# schematic.net
KiCad netlist of a schematic drawn in Altium Designer
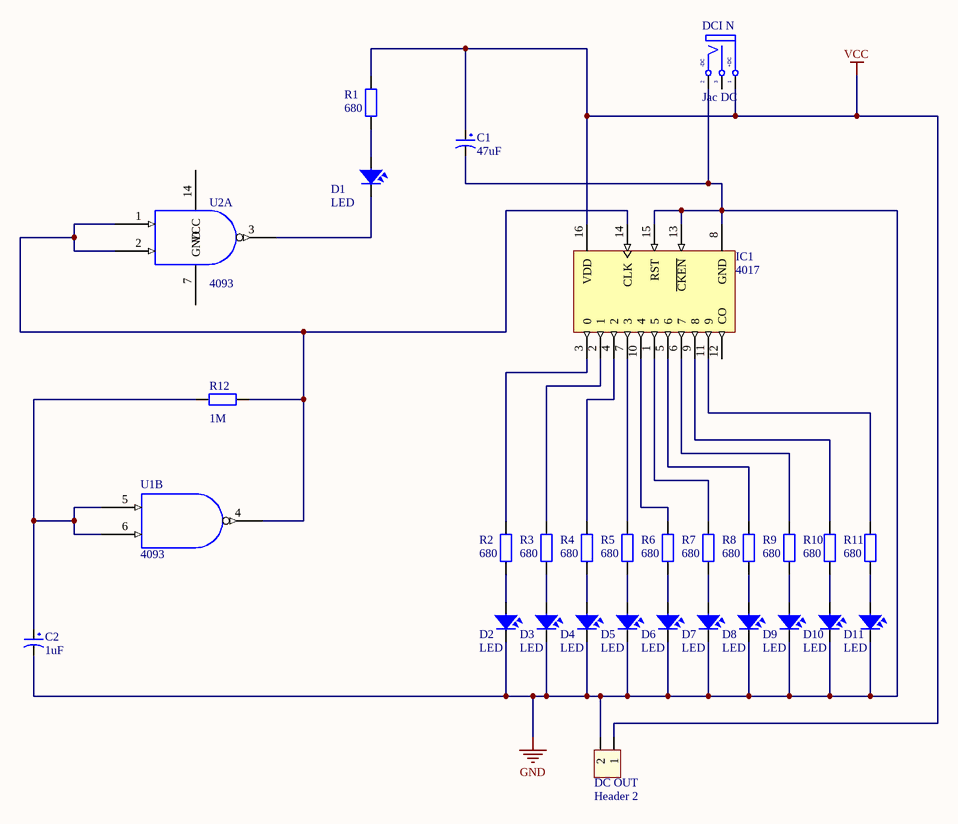
[diagram p0: schematic.SchDoc]

(export (version "E")
  (design (tool "Eeschema 10.0.6"))
  (components
    (comp (ref "C1")
      (value "47uF")
      (footprint "CP1/2.5")
      (description "C 47uF/50V , 220uF/16V")
      (libsource (lib "My Library") (part "CP2"))
    )
    (comp (ref "C2")
      (value "1uF")
      (footprint "CP1/2.5")
      (description "C 47uF/50V , 220uF/16V")
      (libsource (lib "My Library") (part "CP2"))
    )
    (comp (ref "D1")
      (value "LED")
      (footprint "LED-3")
      (description "LED Single colour Green and Red")
      (libsource (lib "My Library") (part "LED"))
    )
    (comp (ref "D2")
      (value "LED")
      (footprint "LED-3")
      (description "LED Single colour Green and Red")
      (libsource (lib "My Library") (part "LED"))
    )
    (comp (ref "D3")
      (value "LED")
      (footprint "LED-3")
      (description "LED Single colour Green and Red")
      (libsource (lib "My Library") (part "LED"))
    )
    (comp (ref "D4")
      (value "LED")
      (footprint "LED-3")
      (description "LED Single colour Green and Red")
      (libsource (lib "My Library") (part "LED"))
    )
    (comp (ref "D5")
      (value "LED")
      (footprint "LED-3")
      (description "LED Single colour Green and Red")
      (libsource (lib "My Library") (part "LED"))
    )
    (comp (ref "D6")
      (value "LED")
      (footprint "LED-3")
      (description "LED Single colour Green and Red")
      (libsource (lib "My Library") (part "LED"))
    )
    (comp (ref "D7")
      (value "LED")
      (footprint "LED-3")
      (description "LED Single colour Green and Red")
      (libsource (lib "My Library") (part "LED"))
    )
    (comp (ref "D8")
      (value "LED")
      (footprint "LED-3")
      (description "LED Single colour Green and Red")
      (libsource (lib "My Library") (part "LED"))
    )
    (comp (ref "D9")
      (value "LED")
      (footprint "LED-3")
      (description "LED Single colour Green and Red")
      (libsource (lib "My Library") (part "LED"))
    )
    (comp (ref "D10")
      (value "LED")
      (footprint "LED-3")
      (description "LED Single colour Green and Red")
      (libsource (lib "My Library") (part "LED"))
    )
    (comp (ref "D11")
      (value "LED")
      (footprint "LED-3")
      (description "LED Single colour Green and Red")
      (libsource (lib "My Library") (part "LED"))
    )
    (comp (ref "DC OUT")
      (value "Header 2")
      (footprint "HED2")
      (description "Header 2 (Green)")
      (libsource (lib "My Library") (part "Hed2"))
    )
    (comp (ref "DCI N")
      (value "Jac DC")
      (footprint "DC-IN")
      (description "Jac DC input")
      (libsource (lib "My Library") (part "DCIN"))
    )
    (comp (ref "IC1")
      (value "4017")
      (footprint "DIP16/W0.3")
      (description "Decade Counter/Divider with 10 Decoded Outputs")
      (fields (field (name "DESIGNED BY") "VanDungEvn"))
      (libsource (lib "My Library") (part "4017"))
    )
    (comp (ref "R1")
      (value "680")
      (footprint "DIEN TRO 1/4 W")
      (description "Resistor")
      (fields (field (name "PUBLISHER") "Altium Limited"))
      (libsource (lib "My Library") (part "Res 1/4 W"))
    )
    (comp (ref "R2")
      (value "680")
      (footprint "DIEN TRO 1/4 W")
      (description "Resistor")
      (fields (field (name "PUBLISHER") "Altium Limited"))
      (libsource (lib "My Library") (part "Res 1/4 W"))
    )
    (comp (ref "R3")
      (value "680")
      (footprint "DIEN TRO 1/4 W")
      (description "Resistor")
      (fields (field (name "PUBLISHER") "Altium Limited"))
      (libsource (lib "My Library") (part "Res 1/4 W"))
    )
    (comp (ref "R4")
      (value "680")
      (footprint "DIEN TRO 1/4 W")
      (description "Resistor")
      (fields (field (name "PUBLISHER") "Altium Limited"))
      (libsource (lib "My Library") (part "Res 1/4 W"))
    )
    (comp (ref "R5")
      (value "680")
      (footprint "DIEN TRO 1/4 W")
      (description "Resistor")
      (fields (field (name "PUBLISHER") "Altium Limited"))
      (libsource (lib "My Library") (part "Res 1/4 W"))
    )
    (comp (ref "R6")
      (value "680")
      (footprint "DIEN TRO 1/4 W")
      (description "Resistor")
      (fields (field (name "PUBLISHER") "Altium Limited"))
      (libsource (lib "My Library") (part "Res 1/4 W"))
    )
    (comp (ref "R7")
      (value "680")
      (footprint "DIEN TRO 1/4 W")
      (description "Resistor")
      (fields (field (name "PUBLISHER") "Altium Limited"))
      (libsource (lib "My Library") (part "Res 1/4 W"))
    )
    (comp (ref "R8")
      (value "680")
      (footprint "DIEN TRO 1/4 W")
      (description "Resistor")
      (fields (field (name "PUBLISHER") "Altium Limited"))
      (libsource (lib "My Library") (part "Res 1/4 W"))
    )
    (comp (ref "R9")
      (value "680")
      (footprint "DIEN TRO 1/4 W")
      (description "Resistor")
      (fields (field (name "PUBLISHER") "Altium Limited"))
      (libsource (lib "My Library") (part "Res 1/4 W"))
    )
    (comp (ref "R10")
      (value "680")
      (footprint "DIEN TRO 1/4 W")
      (description "Resistor")
      (fields (field (name "PUBLISHER") "Altium Limited"))
      (libsource (lib "My Library") (part "Res 1/4 W"))
    )
    (comp (ref "R11")
      (value "680")
      (footprint "DIEN TRO 1/4 W")
      (description "Resistor")
      (fields (field (name "PUBLISHER") "Altium Limited"))
      (libsource (lib "My Library") (part "Res 1/4 W"))
    )
    (comp (ref "R12")
      (value "1M")
      (footprint "DIEN TRO 1/4 W")
      (description "Resistor")
      (fields (field (name "PUBLISHER") "Altium Limited"))
      (libsource (lib "") (part "Res 1/4 W_1"))
    )
    (comp (ref "U1")
      (value "4093")
      (footprint "DIP14")
      (description "Quad 2-INPUT NAND SCHMITT TRIGGER")
      (libsource (lib "My Library") (part "4093"))
    )
    (comp (ref "U2")
      (value "4093")
      (footprint "DIP14")
      (description "Quad 2-INPUT NAND SCHMITT TRIGGER")
      (libsource (lib "My Library") (part "4093"))
    )
  )
  (nets
    (net (code "1") (name "GND") (class "Default")
      (node (ref "C1") (pin "2") (pinfunction "2_2") (pintype "passive"))
      (node (ref "C2") (pin "2") (pinfunction "2_2") (pintype "passive"))
      (node (ref "D10") (pin "2") (pinfunction "2_2") (pintype "passive"))
      (node (ref "D11") (pin "2") (pinfunction "2_2") (pintype "passive"))
      (node (ref "D2") (pin "2") (pinfunction "2_2") (pintype "passive"))
      (node (ref "D3") (pin "2") (pinfunction "2_2") (pintype "passive"))
      (node (ref "D4") (pin "2") (pinfunction "2_2") (pintype "passive"))
      (node (ref "D5") (pin "2") (pinfunction "2_2") (pintype "passive"))
      (node (ref "D6") (pin "2") (pinfunction "2_2") (pintype "passive"))
      (node (ref "D7") (pin "2") (pinfunction "2_2") (pintype "passive"))
      (node (ref "D8") (pin "2") (pinfunction "2_2") (pintype "passive"))
      (node (ref "D9") (pin "2") (pinfunction "2_2") (pintype "passive"))
      (node (ref "DC OUT") (pin "2") (pinfunction "2_2") (pintype "passive"))
      (node (ref "DCI N") (pin "2") (pinfunction "TN_2") (pintype "passive"))
      (node (ref "IC1") (pin "13") (pinfunction "~{CKEN}_13") (pintype "input"))
      (node (ref "IC1") (pin "15") (pinfunction "RST_15") (pintype "input"))
      (node (ref "IC1") (pin "8") (pinfunction "GND_8") (pintype "power_in"))
    )
    (net (code "2") (name "Net-(C2-Pad1)") (class "Default")
      (node (ref "C2") (pin "1") (pinfunction "1_1") (pintype "passive"))
      (node (ref "R12") (pin "2") (pinfunction "2_2") (pintype "passive"))
      (node (ref "U1") (pin "5") (pintype "input"))
      (node (ref "U1") (pin "6") (pintype "input"))
    )
    (net (code "3") (name "Net-(D1-Pad1)") (class "Default")
      (node (ref "D1") (pin "1") (pinfunction "1_1") (pintype "passive"))
      (node (ref "R1") (pin "1") (pinfunction "1_1") (pintype "passive"))
    )
    (net (code "4") (name "Net-(D1-Pad2)") (class "Default")
      (node (ref "D1") (pin "2") (pinfunction "2_2") (pintype "passive"))
      (node (ref "U2") (pin "3") (pintype "output"))
    )
    (net (code "5") (name "Net-(D2-Pad1)") (class "Default")
      (node (ref "D2") (pin "1") (pinfunction "1_1") (pintype "passive"))
      (node (ref "R2") (pin "1") (pinfunction "1_1") (pintype "passive"))
    )
    (net (code "6") (name "Net-(D3-Pad1)") (class "Default")
      (node (ref "D3") (pin "1") (pinfunction "1_1") (pintype "passive"))
      (node (ref "R3") (pin "1") (pinfunction "1_1") (pintype "passive"))
    )
    (net (code "7") (name "Net-(D4-Pad1)") (class "Default")
      (node (ref "D4") (pin "1") (pinfunction "1_1") (pintype "passive"))
      (node (ref "R4") (pin "1") (pinfunction "1_1") (pintype "passive"))
    )
    (net (code "8") (name "Net-(D5-Pad1)") (class "Default")
      (node (ref "D5") (pin "1") (pinfunction "1_1") (pintype "passive"))
      (node (ref "R5") (pin "1") (pinfunction "1_1") (pintype "passive"))
    )
    (net (code "9") (name "Net-(D6-Pad1)") (class "Default")
      (node (ref "D6") (pin "1") (pinfunction "1_1") (pintype "passive"))
      (node (ref "R6") (pin "1") (pinfunction "1_1") (pintype "passive"))
    )
    (net (code "10") (name "Net-(D7-Pad1)") (class "Default")
      (node (ref "D7") (pin "1") (pinfunction "1_1") (pintype "passive"))
      (node (ref "R7") (pin "1") (pinfunction "1_1") (pintype "passive"))
    )
    (net (code "11") (name "Net-(D8-Pad1)") (class "Default")
      (node (ref "D8") (pin "1") (pinfunction "1_1") (pintype "passive"))
      (node (ref "R8") (pin "1") (pinfunction "1_1") (pintype "passive"))
    )
    (net (code "12") (name "Net-(D9-Pad1)") (class "Default")
      (node (ref "D9") (pin "1") (pinfunction "1_1") (pintype "passive"))
      (node (ref "R9") (pin "1") (pinfunction "1_1") (pintype "passive"))
    )
    (net (code "13") (name "Net-(D10-Pad1)") (class "Default")
      (node (ref "D10") (pin "1") (pinfunction "1_1") (pintype "passive"))
      (node (ref "R10") (pin "1") (pinfunction "1_1") (pintype "passive"))
    )
    (net (code "14") (name "Net-(D11-Pad1)") (class "Default")
      (node (ref "D11") (pin "1") (pinfunction "1_1") (pintype "passive"))
      (node (ref "R11") (pin "1") (pinfunction "1_1") (pintype "passive"))
    )
    (net (code "15") (name "Net-(IC1-0)") (class "Default")
      (node (ref "IC1") (pin "3") (pinfunction "0_3") (pintype "output"))
      (node (ref "R2") (pin "2") (pinfunction "2_2") (pintype "passive"))
    )
    (net (code "16") (name "Net-(IC1-1)") (class "Default")
      (node (ref "IC1") (pin "2") (pinfunction "1_2") (pintype "output"))
      (node (ref "R3") (pin "2") (pinfunction "2_2") (pintype "passive"))
    )
    (net (code "17") (name "Net-(IC1-2)") (class "Default")
      (node (ref "IC1") (pin "4") (pinfunction "2_4") (pintype "output"))
      (node (ref "R4") (pin "2") (pinfunction "2_2") (pintype "passive"))
    )
    (net (code "18") (name "Net-(IC1-3)") (class "Default")
      (node (ref "IC1") (pin "7") (pinfunction "3_7") (pintype "output"))
      (node (ref "R5") (pin "2") (pinfunction "2_2") (pintype "passive"))
    )
    (net (code "19") (name "Net-(IC1-4)") (class "Default")
      (node (ref "IC1") (pin "10") (pinfunction "4_10") (pintype "output"))
      (node (ref "R6") (pin "2") (pinfunction "2_2") (pintype "passive"))
    )
    (net (code "20") (name "Net-(IC1-5)") (class "Default")
      (node (ref "IC1") (pin "1") (pinfunction "5_1") (pintype "output"))
      (node (ref "R7") (pin "2") (pinfunction "2_2") (pintype "passive"))
    )
    (net (code "21") (name "Net-(IC1-6)") (class "Default")
      (node (ref "IC1") (pin "5") (pinfunction "6_5") (pintype "output"))
      (node (ref "R8") (pin "2") (pinfunction "2_2") (pintype "passive"))
    )
    (net (code "22") (name "Net-(IC1-7)") (class "Default")
      (node (ref "IC1") (pin "6") (pinfunction "7_6") (pintype "output"))
      (node (ref "R9") (pin "2") (pinfunction "2_2") (pintype "passive"))
    )
    (net (code "23") (name "Net-(IC1-8)") (class "Default")
      (node (ref "IC1") (pin "9") (pinfunction "8_9") (pintype "output"))
      (node (ref "R10") (pin "2") (pinfunction "2_2") (pintype "passive"))
    )
    (net (code "24") (name "Net-(IC1-9)") (class "Default")
      (node (ref "IC1") (pin "11") (pinfunction "9_11") (pintype "output"))
      (node (ref "R11") (pin "2") (pinfunction "2_2") (pintype "passive"))
    )
    (net (code "25") (name "Net-(IC1-CLK)") (class "Default")
      (node (ref "IC1") (pin "14") (pinfunction "CLK_14") (pintype "input"))
      (node (ref "R12") (pin "1") (pinfunction "1_1") (pintype "passive"))
      (node (ref "U1") (pin "4") (pintype "output"))
      (node (ref "U2") (pin "1") (pintype "input"))
      (node (ref "U2") (pin "2") (pintype "input"))
    )
    (net (code "26") (name "VCC") (class "Default")
      (node (ref "C1") (pin "1") (pinfunction "1_1") (pintype "passive"))
      (node (ref "DC OUT") (pin "1") (pinfunction "1_1") (pintype "passive"))
      (node (ref "DCI N") (pin "1") (pinfunction "T_1") (pintype "passive"))
      (node (ref "IC1") (pin "16") (pinfunction "VDD_16") (pintype "power_in"))
      (node (ref "R1") (pin "2") (pinfunction "2_2") (pintype "passive"))
    )
    (net (code "27") (name "unconnected-(DCI N-S-Pad3)") (class "Default")
      (node (ref "DCI N") (pin "3") (pinfunction "S_3") (pintype "power_in"))
    )
    (net (code "28") (name "unconnected-(IC1-CO-Pad12)") (class "Default")
      (node (ref "IC1") (pin "12") (pinfunction "CO_12") (pintype "output"))
    )
    (net (code "29") (name "unconnected-(U2A-GND-Pad7)") (class "Default")
      (node (ref "U2") (pin "7") (pinfunction "GND_7") (pintype "power_in"))
    )
    (net (code "30") (name "unconnected-(U2A-VCC-Pad14)") (class "Default")
      (node (ref "U2") (pin "14") (pinfunction "VCC_14") (pintype "power_in"))
    )
  )
)
